# ESP_ART_NET.net
KiCad netlist of a schematic drawn in EAGLE
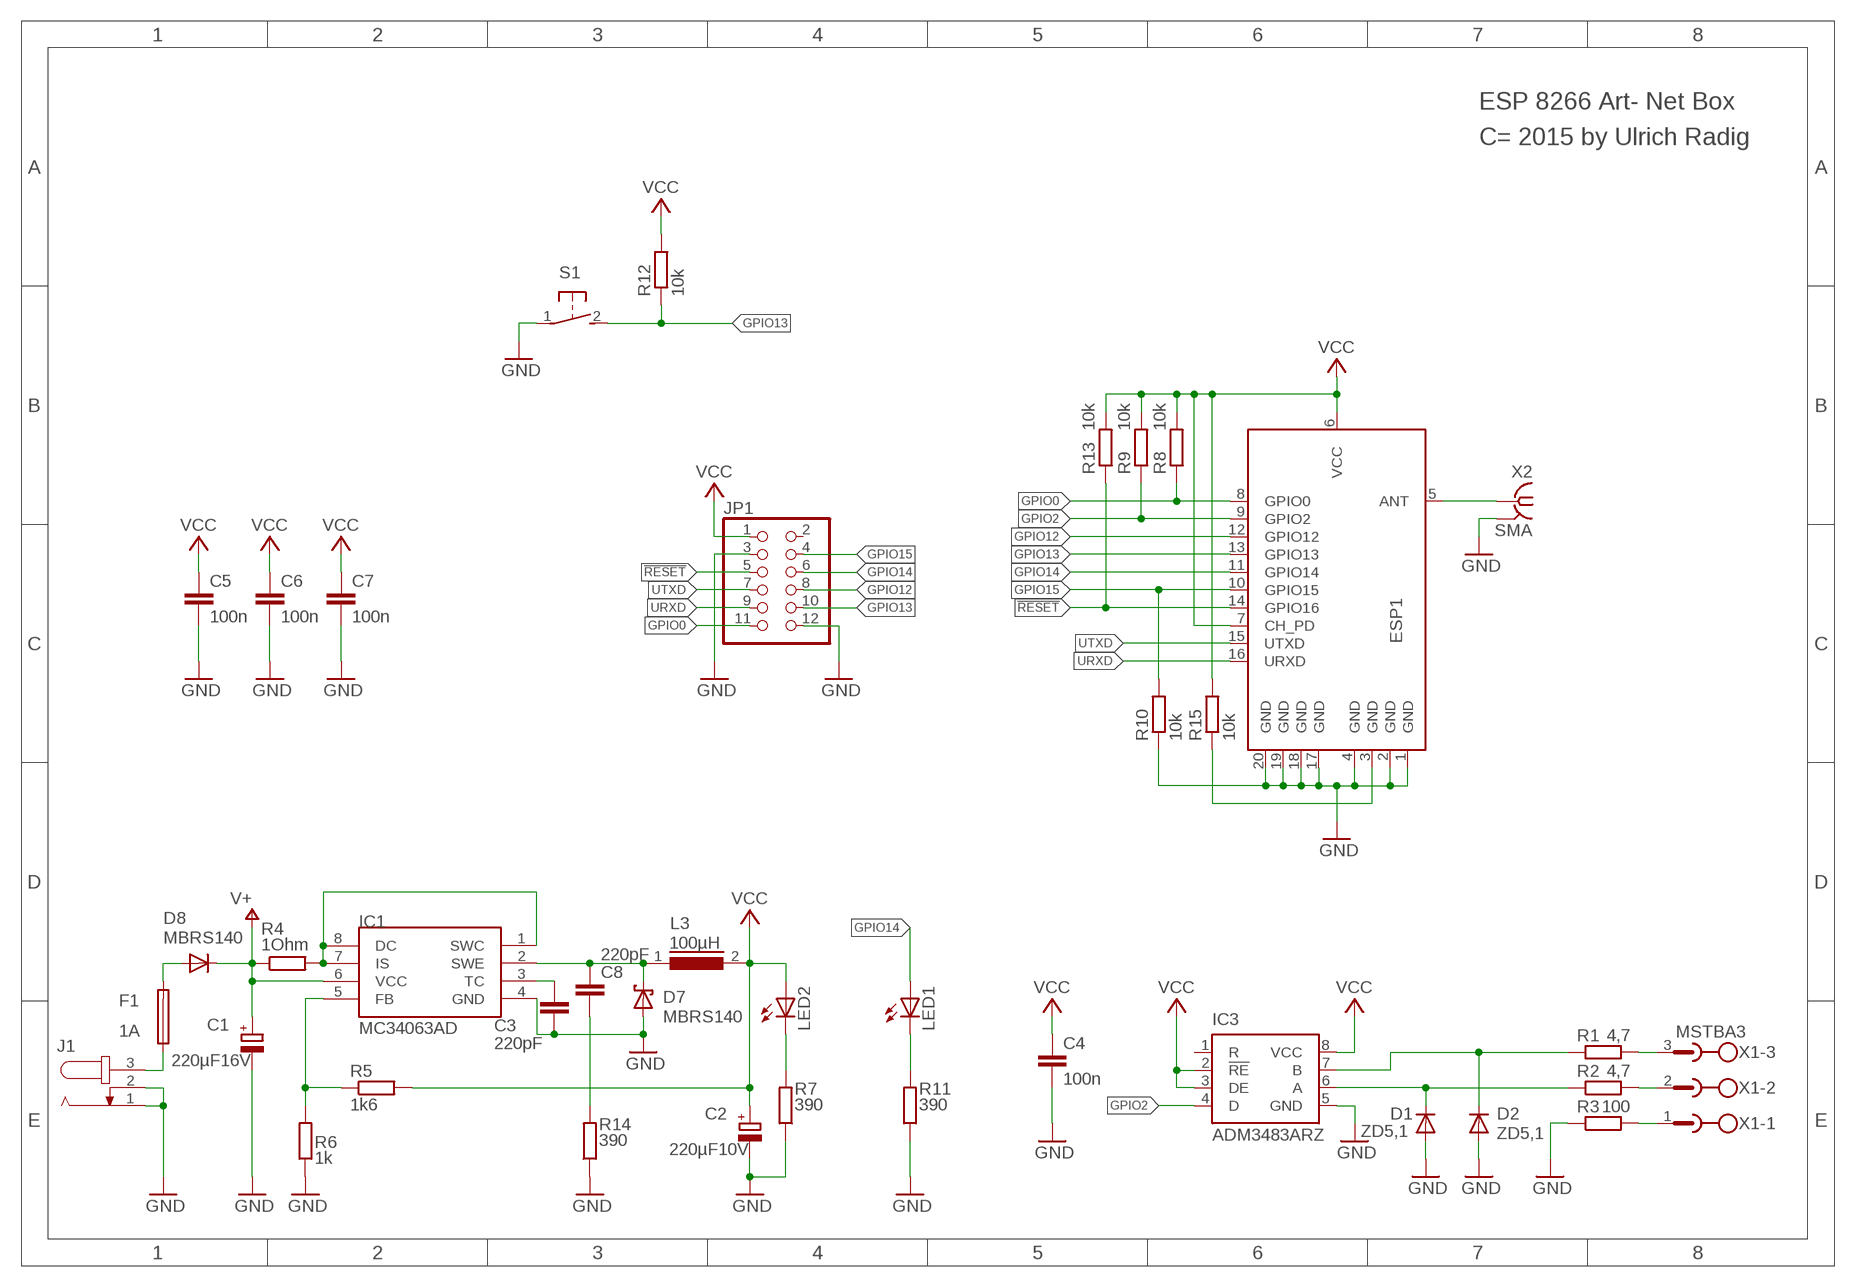
[diagram p0: schematic, sheet 1]

(export (version "E")
  (design (tool "Eeschema 10.0.6"))
  (components
    (comp (ref "C1")
      (value "220µF16V")
      (footprint "eagle-import:E5-8,5")
      (libsource (lib "eagle-import") (part "CPOL-EUE5-8.5"))
    )
    (comp (ref "C2")
      (value "220µF10V")
      (footprint "eagle-import:E2,5-7")
      (libsource (lib "eagle-import") (part "CPOL-EUE2.5-7"))
    )
    (comp (ref "C3")
      (value "220pF")
      (footprint "eagle-import:C0805")
      (libsource (lib "eagle-import") (part "C-EUC0805"))
    )
    (comp (ref "C4")
      (value "100n")
      (footprint "eagle-import:C0805")
      (libsource (lib "eagle-import") (part "C-EUC0805"))
    )
    (comp (ref "C5")
      (value "100n")
      (footprint "eagle-import:C0805")
      (libsource (lib "eagle-import") (part "C-EUC0805"))
    )
    (comp (ref "C6")
      (value "100n")
      (footprint "eagle-import:C0805")
      (libsource (lib "eagle-import") (part "C-EUC0805"))
    )
    (comp (ref "C7")
      (value "100n")
      (footprint "eagle-import:C0805")
      (libsource (lib "eagle-import") (part "C-EUC0805"))
    )
    (comp (ref "C8")
      (value "220pF")
      (footprint "eagle-import:C0805")
      (libsource (lib "eagle-import") (part "C-EUC0805"))
    )
    (comp (ref "D1")
      (value "ZD5,1")
      (footprint "eagle-import:SOD80C")
      (libsource (lib "eagle-import") (part "PMLL4150"))
    )
    (comp (ref "D2")
      (value "ZD5,1")
      (footprint "eagle-import:SOD80C")
      (libsource (lib "eagle-import") (part "PMLL4150"))
    )
    (comp (ref "D7")
      (value "MBRS140")
      (footprint "eagle-import:SMB")
      (libsource (lib "eagle-import") (part "SCHOTTKY-DIODESMD"))
    )
    (comp (ref "D8")
      (value "MBRS140")
      (footprint "eagle-import:SMB")
      (libsource (lib "eagle-import") (part "DIODE-SMB"))
    )
    (comp (ref "ESP1")
      (value "ESP8266MOD")
      (footprint "eagle-import:ESP8266MOD")
      (libsource (lib "eagle-import") (part "ESP8266MOD"))
    )
    (comp (ref "F1")
      (value "1A")
      (footprint "eagle-import:PICOFUSE")
      (libsource (lib "eagle-import") (part "PICOFUSE"))
    )
    (comp (ref "IC1")
      (value "MC34063AD")
      (footprint "eagle-import:SOIC8")
      (libsource (lib "eagle-import") (part "MC34063AD"))
    )
    (comp (ref "IC3")
      (value "ADM3483ARZ")
      (footprint "eagle-import:SO-08")
      (libsource (lib "eagle-import") (part "SN65176D"))
    )
    (comp (ref "J1")
      (value "JACK-PLUG1")
      (footprint "eagle-import:SPC4078")
      (libsource (lib "eagle-import") (part "JACK-PLUG1"))
    )
    (comp (ref "JP1")
      (value "PINHD-2X6")
      (footprint "eagle-import:2X06")
      (libsource (lib "eagle-import") (part "PINHD-2X6"))
    )
    (comp (ref "L3")
      (value "100µH")
      (footprint "eagle-import:SLF7045")
      (libsource (lib "eagle-import") (part "SLF7045"))
    )
    (comp (ref "LED1")
      (value "LEDCHIPLED_1206")
      (footprint "eagle-import:CHIPLED_1206")
      (libsource (lib "eagle-import") (part "LEDCHIPLED_1206"))
    )
    (comp (ref "LED2")
      (value "LEDCHIPLED_1206")
      (footprint "eagle-import:CHIPLED_1206")
      (libsource (lib "eagle-import") (part "LEDCHIPLED_1206"))
    )
    (comp (ref "R1")
      (value "4,7")
      (footprint "eagle-import:R0805")
      (libsource (lib "eagle-import") (part "R-EU_R0805"))
    )
    (comp (ref "R2")
      (value "4,7")
      (footprint "eagle-import:R0805")
      (libsource (lib "eagle-import") (part "R-EU_R0805"))
    )
    (comp (ref "R3")
      (value "100")
      (footprint "eagle-import:R0805")
      (libsource (lib "eagle-import") (part "R-EU_R0805"))
    )
    (comp (ref "R4")
      (value "1Ohm")
      (footprint "eagle-import:0207_10")
      (libsource (lib "eagle-import") (part "R-EU_0207/10"))
    )
    (comp (ref "R5")
      (value "1k6")
      (footprint "eagle-import:M0805")
      (libsource (lib "eagle-import") (part "R-EU_M0805"))
    )
    (comp (ref "R6")
      (value "1k")
      (footprint "eagle-import:M0805")
      (libsource (lib "eagle-import") (part "R-EU_M0805"))
    )
    (comp (ref "R7")
      (value "390")
      (footprint "eagle-import:R0805")
      (libsource (lib "eagle-import") (part "R-EU_R0805"))
    )
    (comp (ref "R8")
      (value "10k")
      (footprint "eagle-import:R0805")
      (libsource (lib "eagle-import") (part "R-EU_R0805"))
    )
    (comp (ref "R9")
      (value "10k")
      (footprint "eagle-import:R0805")
      (libsource (lib "eagle-import") (part "R-EU_R0805"))
    )
    (comp (ref "R10")
      (value "10k")
      (footprint "eagle-import:R0805")
      (libsource (lib "eagle-import") (part "R-EU_R0805"))
    )
    (comp (ref "R11")
      (value "390")
      (footprint "eagle-import:R0805")
      (libsource (lib "eagle-import") (part "R-EU_R0805"))
    )
    (comp (ref "R12")
      (value "10k")
      (footprint "eagle-import:R0805")
      (libsource (lib "eagle-import") (part "R-EU_R0805"))
    )
    (comp (ref "R13")
      (value "10k")
      (footprint "eagle-import:R0805")
      (libsource (lib "eagle-import") (part "R-EU_R0805"))
    )
    (comp (ref "R14")
      (value "390")
      (footprint "eagle-import:R0805")
      (libsource (lib "eagle-import") (part "R-EU_R0805"))
    )
    (comp (ref "R15")
      (value "10k")
      (footprint "eagle-import:R0805")
      (libsource (lib "eagle-import") (part "R-EU_R0805"))
    )
    (comp (ref "S1")
      (value "31-XX")
      (footprint "eagle-import:B3F-31XX")
      (libsource (lib "eagle-import") (part "31-XX"))
    )
    (comp (ref "X1")
      (value "MSTBA3")
      (footprint "eagle-import:MSTBA3")
      (libsource (lib "eagle-import") (part "MSTBA3"))
    )
    (comp (ref "X2")
      (value "SMA")
      (footprint "eagle-import:J502-ND-142-0701-801_806")
      (libsource (lib "eagle-import") (part "SMA-142-0701-801/806"))
    )
  )
  (nets
    (net (code "1") (name "/~{RESET}") (class "Default")
      (node (ref "ESP1") (pin "14") (pinfunction "GPIO16_14") (pintype "bidirectional"))
      (node (ref "JP1") (pin "5") (pinfunction "5_5") (pintype "passive"))
      (node (ref "R13") (pin "1") (pinfunction "1_1") (pintype "passive"))
    )
    (net (code "2") (name "GND") (class "Default")
      (node (ref "C1") (pin "-") (pinfunction "-_-") (pintype "passive"))
      (node (ref "C2") (pin "-") (pinfunction "-_-") (pintype "passive"))
      (node (ref "C3") (pin "2") (pinfunction "2_2") (pintype "passive"))
      (node (ref "C4") (pin "2") (pinfunction "2_2") (pintype "passive"))
      (node (ref "C5") (pin "2") (pinfunction "2_2") (pintype "passive"))
      (node (ref "C6") (pin "2") (pinfunction "2_2") (pintype "passive"))
      (node (ref "C7") (pin "2") (pinfunction "2_2") (pintype "passive"))
      (node (ref "D1") (pin "A") (pinfunction "A_A") (pintype "passive"))
      (node (ref "D2") (pin "A") (pinfunction "A_A") (pintype "passive"))
      (node (ref "D7") (pin "A") (pinfunction "A_A") (pintype "passive"))
      (node (ref "ESP1") (pin "1") (pinfunction "GND_1") (pintype "bidirectional"))
      (node (ref "ESP1") (pin "17") (pinfunction "GND_17") (pintype "bidirectional"))
      (node (ref "ESP1") (pin "18") (pinfunction "GND_18") (pintype "bidirectional"))
      (node (ref "ESP1") (pin "19") (pinfunction "GND_19") (pintype "bidirectional"))
      (node (ref "ESP1") (pin "2") (pinfunction "GND_2") (pintype "bidirectional"))
      (node (ref "ESP1") (pin "20") (pinfunction "GND_20") (pintype "bidirectional"))
      (node (ref "ESP1") (pin "4") (pinfunction "GND_4") (pintype "bidirectional"))
      (node (ref "IC1") (pin "4") (pinfunction "GND_4") (pintype "passive"))
      (node (ref "IC3") (pin "5") (pinfunction "GND_5") (pintype "input"))
      (node (ref "J1") (pin "1") (pinfunction "1_1") (pintype "passive"))
      (node (ref "J1") (pin "2") (pinfunction "2_2") (pintype "passive"))
      (node (ref "JP1") (pin "12") (pinfunction "12_12") (pintype "passive"))
      (node (ref "JP1") (pin "3") (pinfunction "3_3") (pintype "passive"))
      (node (ref "R10") (pin "1") (pinfunction "1_1") (pintype "passive"))
      (node (ref "R11") (pin "1") (pinfunction "1_1") (pintype "passive"))
      (node (ref "R14") (pin "1") (pinfunction "1_1") (pintype "passive"))
      (node (ref "R3") (pin "1") (pinfunction "1_1") (pintype "passive"))
      (node (ref "R6") (pin "1") (pinfunction "1_1") (pintype "passive"))
      (node (ref "R7") (pin "1") (pinfunction "1_1") (pintype "passive"))
      (node (ref "S1") (pin "1") (pinfunction "P_1") (pintype "passive"))
      (node (ref "X2") (pin "G@1") (pinfunction "GND_G@1") (pintype "power_in"))
    )
    (net (code "3") (name "GPIO0") (class "Default")
      (node (ref "ESP1") (pin "8") (pinfunction "GPIO0_8") (pintype "bidirectional"))
      (node (ref "JP1") (pin "11") (pinfunction "11_11") (pintype "passive"))
      (node (ref "R8") (pin "1") (pinfunction "1_1") (pintype "passive"))
    )
    (net (code "4") (name "GPIO2") (class "Default")
      (node (ref "ESP1") (pin "9") (pinfunction "GPIO2_9") (pintype "bidirectional"))
      (node (ref "IC3") (pin "4") (pinfunction "D_4") (pintype "input"))
      (node (ref "R9") (pin "1") (pinfunction "1_1") (pintype "passive"))
    )
    (net (code "5") (name "GPIO12") (class "Default")
      (node (ref "ESP1") (pin "12") (pinfunction "GPIO12_12") (pintype "bidirectional"))
      (node (ref "JP1") (pin "8") (pinfunction "8_8") (pintype "passive"))
    )
    (net (code "6") (name "GPIO13") (class "Default")
      (node (ref "ESP1") (pin "13") (pinfunction "GPIO13_13") (pintype "bidirectional"))
      (node (ref "JP1") (pin "10") (pinfunction "10_10") (pintype "passive"))
      (node (ref "R12") (pin "1") (pinfunction "1_1") (pintype "passive"))
      (node (ref "S1") (pin "2") (pinfunction "S_2") (pintype "passive"))
    )
    (net (code "7") (name "GPIO14") (class "Default")
      (node (ref "ESP1") (pin "11") (pinfunction "GPIO14_11") (pintype "bidirectional"))
      (node (ref "JP1") (pin "6") (pinfunction "6_6") (pintype "passive"))
      (node (ref "LED1") (pin "A") (pinfunction "A_A") (pintype "passive"))
    )
    (net (code "8") (name "GPIO15") (class "Default")
      (node (ref "ESP1") (pin "10") (pinfunction "GPIO15_10") (pintype "bidirectional"))
      (node (ref "JP1") (pin "4") (pinfunction "4_4") (pintype "passive"))
      (node (ref "R10") (pin "2") (pinfunction "2_2") (pintype "passive"))
    )
    (net (code "9") (name "Net-(C8-Pad2)") (class "Default")
      (node (ref "C8") (pin "2") (pinfunction "2_2") (pintype "passive"))
      (node (ref "R14") (pin "2") (pinfunction "2_2") (pintype "passive"))
    )
    (net (code "10") (name "Net-(D8-PadA)") (class "Default")
      (node (ref "D8") (pin "A") (pinfunction "A_A") (pintype "passive"))
      (node (ref "F1") (pin "2") (pinfunction "2_2") (pintype "passive"))
    )
    (net (code "11") (name "Net-(ESP1-ANT)") (class "Default")
      (node (ref "ESP1") (pin "5") (pinfunction "ANT_5") (pintype "bidirectional"))
      (node (ref "X2") (pin "1") (pinfunction "1_1") (pintype "passive"))
    )
    (net (code "12") (name "Net-(ESP1-GND-Pad3)") (class "Default")
      (node (ref "ESP1") (pin "3") (pinfunction "GND_3") (pintype "bidirectional"))
      (node (ref "R15") (pin "1") (pinfunction "1_1") (pintype "passive"))
    )
    (net (code "13") (name "Net-(F1-Pad1)") (class "Default")
      (node (ref "F1") (pin "1") (pinfunction "1_1") (pintype "passive"))
      (node (ref "J1") (pin "3") (pinfunction "3_3") (pintype "passive"))
    )
    (net (code "14") (name "Net-(IC1-DC)") (class "Default")
      (node (ref "IC1") (pin "1") (pinfunction "SWC_1") (pintype "passive"))
      (node (ref "IC1") (pin "7") (pinfunction "IS_7") (pintype "passive"))
      (node (ref "IC1") (pin "8") (pinfunction "DC_8") (pintype "passive"))
      (node (ref "R4") (pin "2") (pinfunction "2_2") (pintype "passive"))
    )
    (net (code "15") (name "Net-(IC1-FB)") (class "Default")
      (node (ref "IC1") (pin "5") (pinfunction "FB_5") (pintype "passive"))
      (node (ref "R5") (pin "1") (pinfunction "1_1") (pintype "passive"))
      (node (ref "R6") (pin "2") (pinfunction "2_2") (pintype "passive"))
    )
    (net (code "16") (name "Net-(IC1-SWE)") (class "Default")
      (node (ref "C8") (pin "1") (pinfunction "1_1") (pintype "passive"))
      (node (ref "D7") (pin "C") (pinfunction "C_C") (pintype "passive"))
      (node (ref "IC1") (pin "2") (pinfunction "SWE_2") (pintype "passive"))
      (node (ref "L3") (pin "1") (pinfunction "1_1") (pintype "passive"))
    )
    (net (code "17") (name "Net-(IC1-TC)") (class "Default")
      (node (ref "C3") (pin "1") (pinfunction "1_1") (pintype "passive"))
      (node (ref "IC1") (pin "3") (pinfunction "TC_3") (pintype "passive"))
    )
    (net (code "18") (name "Net-(IC3-A)") (class "Default")
      (node (ref "D1") (pin "C") (pinfunction "C_C") (pintype "passive"))
      (node (ref "IC3") (pin "6") (pinfunction "A_6") (pintype "input"))
      (node (ref "R2") (pin "1") (pinfunction "1_1") (pintype "passive"))
    )
    (net (code "19") (name "Net-(IC3-B)") (class "Default")
      (node (ref "D2") (pin "C") (pinfunction "C_C") (pintype "passive"))
      (node (ref "IC3") (pin "7") (pinfunction "B_7") (pintype "input"))
      (node (ref "R1") (pin "1") (pinfunction "1_1") (pintype "passive"))
    )
    (net (code "20") (name "Net-(LED1-PadC)") (class "Default")
      (node (ref "LED1") (pin "C") (pinfunction "C_C") (pintype "passive"))
      (node (ref "R11") (pin "2") (pinfunction "2_2") (pintype "passive"))
    )
    (net (code "21") (name "Net-(LED2-PadC)") (class "Default")
      (node (ref "LED2") (pin "C") (pinfunction "C_C") (pintype "passive"))
      (node (ref "R7") (pin "2") (pinfunction "2_2") (pintype "passive"))
    )
    (net (code "22") (name "Net-(R3-Pad2)") (class "Default")
      (node (ref "R3") (pin "2") (pinfunction "2_2") (pintype "passive"))
      (node (ref "X1") (pin "1") (pinfunction "1_1") (pintype "passive"))
    )
    (net (code "23") (name "Net-(X1B-1)") (class "Default")
      (node (ref "R2") (pin "2") (pinfunction "2_2") (pintype "passive"))
      (node (ref "X1") (pin "2") (pinfunction "1_2") (pintype "passive"))
    )
    (net (code "24") (name "Net-(X1C-1)") (class "Default")
      (node (ref "R1") (pin "2") (pinfunction "2_2") (pintype "passive"))
      (node (ref "X1") (pin "3") (pinfunction "1_3") (pintype "passive"))
    )
    (net (code "25") (name "URXD") (class "Default")
      (node (ref "ESP1") (pin "16") (pinfunction "URXD_16") (pintype "bidirectional"))
      (node (ref "JP1") (pin "9") (pinfunction "9_9") (pintype "passive"))
    )
    (net (code "26") (name "UTXD") (class "Default")
      (node (ref "ESP1") (pin "15") (pinfunction "UTXD_15") (pintype "bidirectional"))
      (node (ref "JP1") (pin "7") (pinfunction "7_7") (pintype "passive"))
    )
    (net (code "27") (name "V+") (class "Default")
      (node (ref "C1") (pin "+") (pinfunction "+_+") (pintype "passive"))
      (node (ref "D8") (pin "C") (pinfunction "C_C") (pintype "passive"))
      (node (ref "IC1") (pin "6") (pinfunction "VCC_6") (pintype "passive"))
      (node (ref "R4") (pin "1") (pinfunction "1_1") (pintype "passive"))
    )
    (net (code "28") (name "VCC") (class "Default")
      (node (ref "C2") (pin "+") (pinfunction "+_+") (pintype "passive"))
      (node (ref "C4") (pin "1") (pinfunction "1_1") (pintype "passive"))
      (node (ref "C5") (pin "1") (pinfunction "1_1") (pintype "passive"))
      (node (ref "C6") (pin "1") (pinfunction "1_1") (pintype "passive"))
      (node (ref "C7") (pin "1") (pinfunction "1_1") (pintype "passive"))
      (node (ref "ESP1") (pin "6") (pinfunction "VCC_6") (pintype "bidirectional"))
      (node (ref "ESP1") (pin "7") (pinfunction "CH_PD_7") (pintype "bidirectional"))
      (node (ref "IC3") (pin "2") (pinfunction "~{RE}_2") (pintype "input"))
      (node (ref "IC3") (pin "3") (pinfunction "DE_3") (pintype "input"))
      (node (ref "IC3") (pin "8") (pinfunction "VCC_8") (pintype "input"))
      (node (ref "JP1") (pin "1") (pinfunction "1_1") (pintype "passive"))
      (node (ref "L3") (pin "2") (pinfunction "2_2") (pintype "passive"))
      (node (ref "LED2") (pin "A") (pinfunction "A_A") (pintype "passive"))
      (node (ref "R12") (pin "2") (pinfunction "2_2") (pintype "passive"))
      (node (ref "R13") (pin "2") (pinfunction "2_2") (pintype "passive"))
      (node (ref "R15") (pin "2") (pinfunction "2_2") (pintype "passive"))
      (node (ref "R5") (pin "2") (pinfunction "2_2") (pintype "passive"))
      (node (ref "R8") (pin "2") (pinfunction "2_2") (pintype "passive"))
      (node (ref "R9") (pin "2") (pinfunction "2_2") (pintype "passive"))
    )
    (net (code "29") (name "unconnected-(IC3-R-Pad1)") (class "Default")
      (node (ref "IC3") (pin "1") (pinfunction "R_1") (pintype "input"))
    )
    (net (code "30") (name "unconnected-(JP1-Pad2)") (class "Default")
      (node (ref "JP1") (pin "2") (pinfunction "2_2") (pintype "passive"))
    )
  )
)
